# Quectel-1280.net
KiCad netlist of a schematic drawn in EAGLE
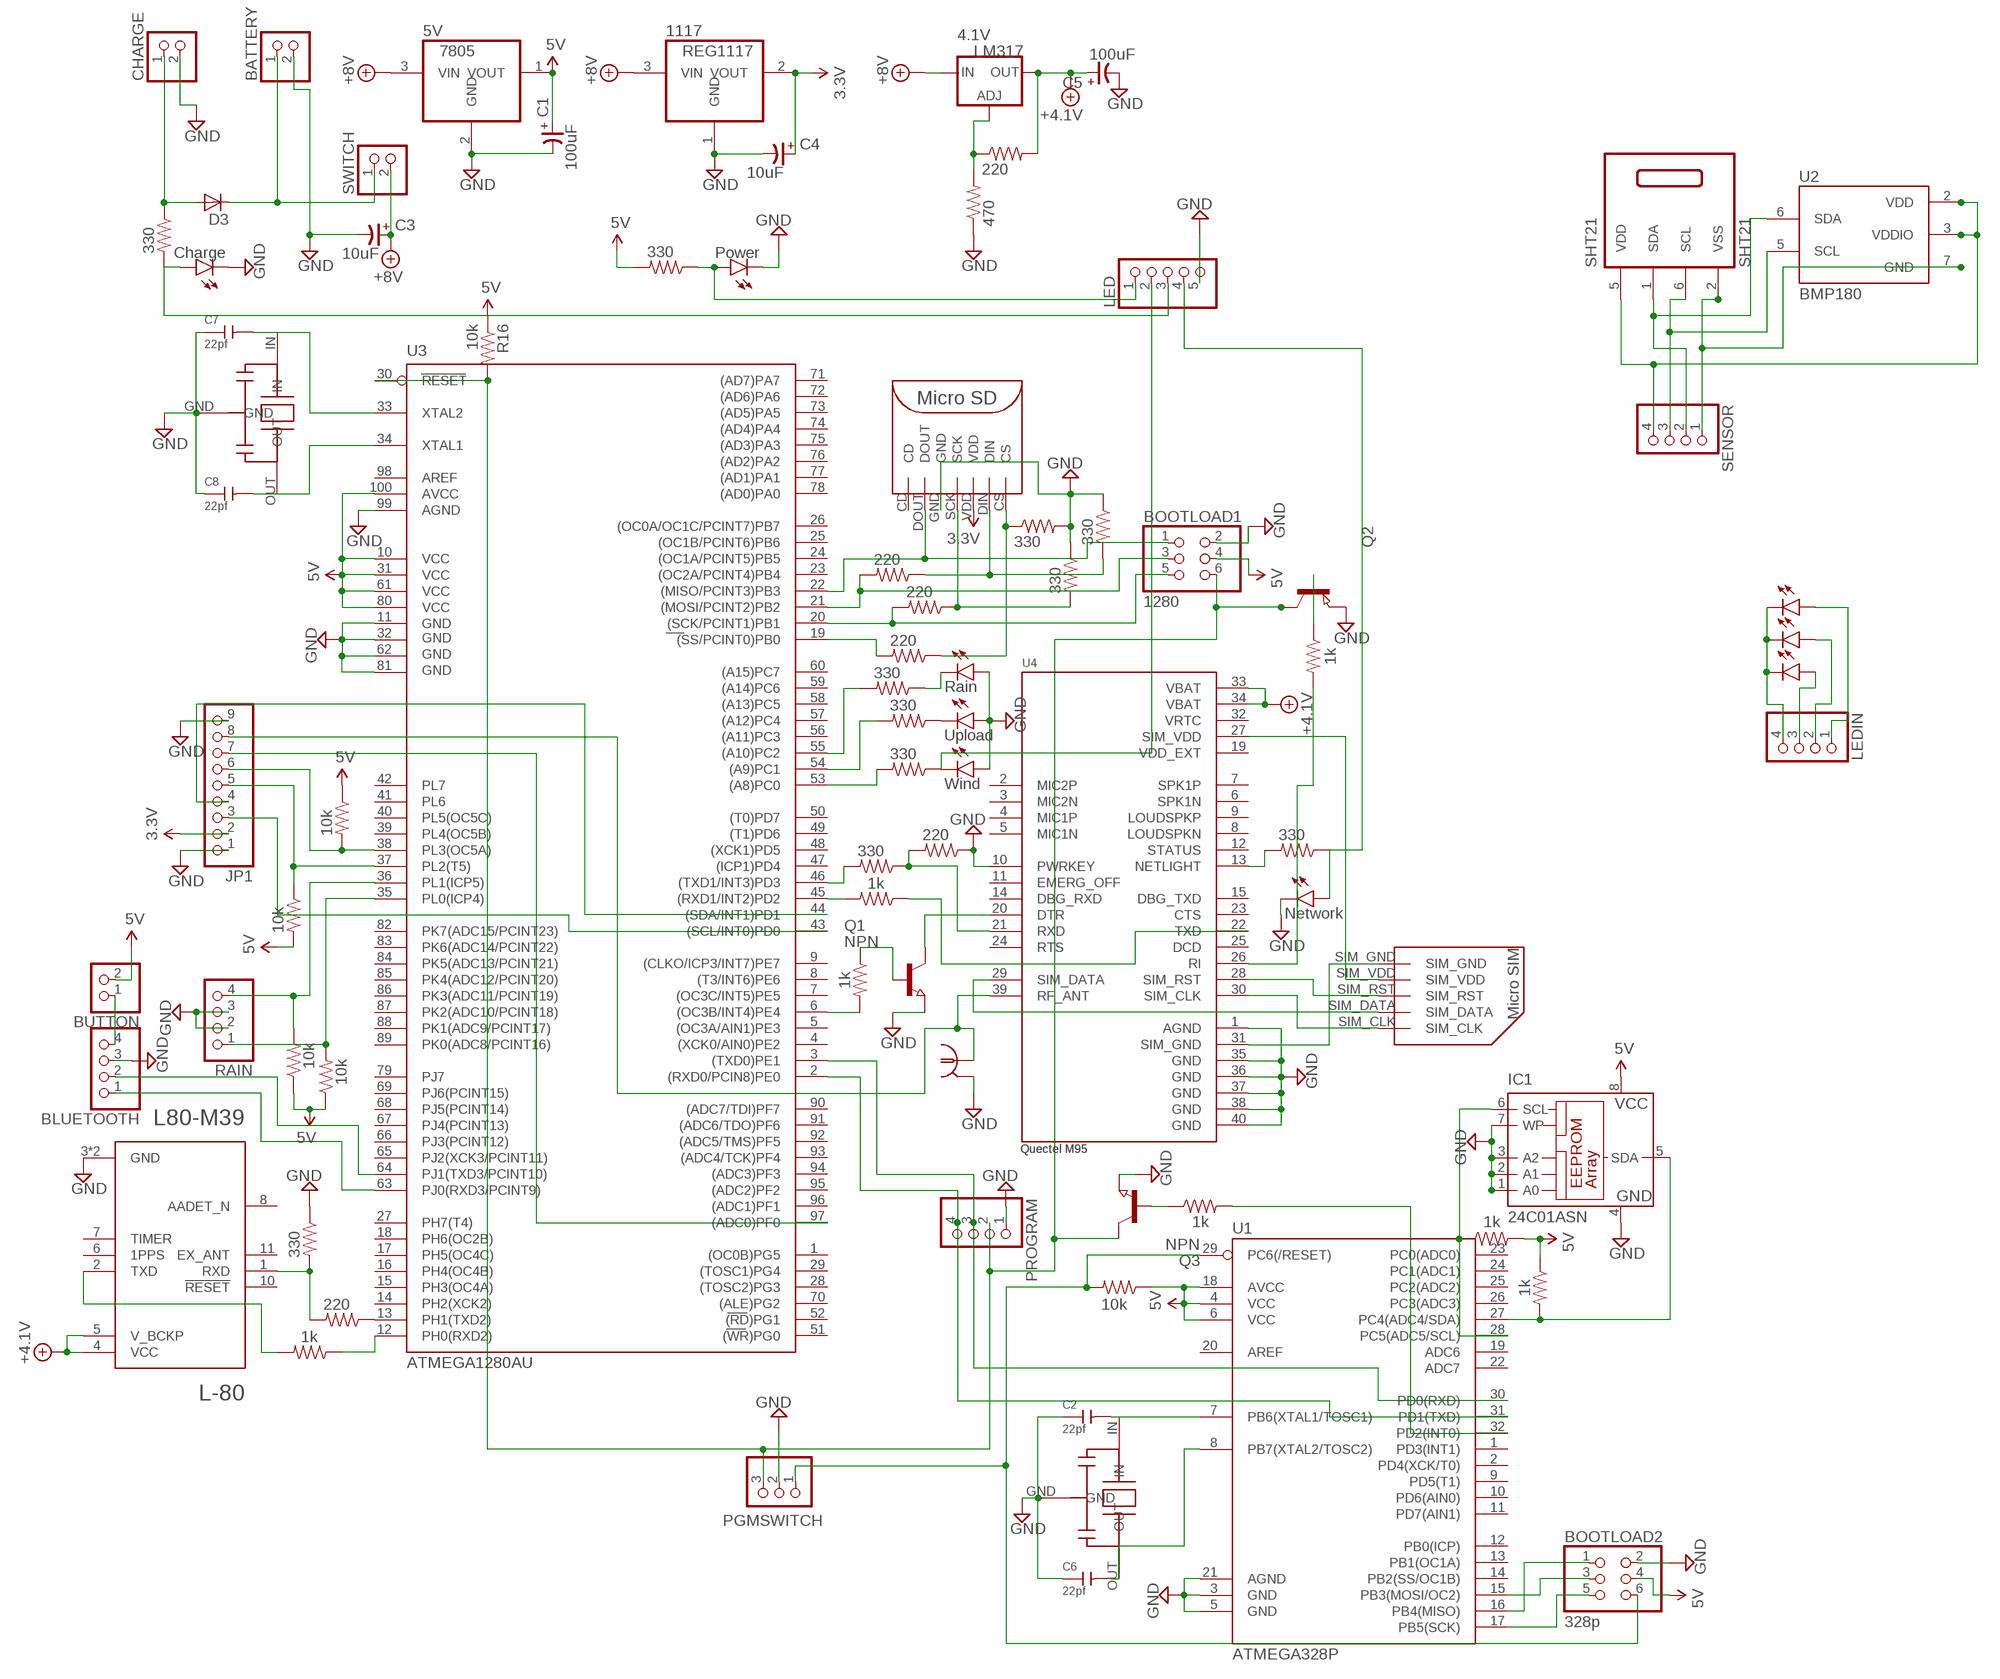
[diagram p0: schematic, sheet 1]

(export (version "E")
  (design (tool "Eeschema 10.0.6"))
  (components
    (comp (ref "4.1V")
      (value "LM317")
      (footprint "eagle-import:DPACK")
      (libsource (lib "eagle-import") (part "v-reg_LM317?MABDT"))
    )
    (comp (ref "5V")
      (value "7805")
      (footprint "eagle-import:SOT223")
      (fields (field (name "MPN") "REG1118-2.85/2K5G4") (field (name "MPN_1") "7805"))
      (libsource (lib "eagle-import") (part "REG1118"))
    )
    (comp (ref "1117")
      (value "REG1117")
      (footprint "eagle-import:SOT223")
      (libsource (lib "eagle-import") (part "REG1117"))
    )
    (comp (ref "ANT")
      (value "LTI-SASF54GT")
      (footprint "eagle-import:LTI-SASF54GT")
      (libsource (lib "eagle-import") (part "LTI-SASF54GT"))
    )
    (comp (ref "BATTERY")
      (value "PINHD-1X2")
      (footprint "eagle-import:1X02")
      (libsource (lib "eagle-import") (part "PINHD-1X2"))
    )
    (comp (ref "BLUETOOTH")
      (value "PINHD-1X4")
      (footprint "eagle-import:1X04")
      (libsource (lib "eagle-import") (part "PINHD-1X4"))
    )
    (comp (ref "BOOTLOAD1")
      (value "1280")
      (footprint "eagle-import:2X03")
      (libsource (lib "eagle-import") (part "PINHD-2X3"))
    )
    (comp (ref "BOOTLOAD2")
      (value "328p")
      (footprint "eagle-import:2X03")
      (libsource (lib "eagle-import") (part "PINHD-2X3"))
    )
    (comp (ref "BUTTON")
      (value "PINHD-1X2")
      (footprint "eagle-import:1X02")
      (libsource (lib "eagle-import") (part "PINHD-1X2"))
    )
    (comp (ref "C1")
      (value "100uF")
      (footprint "eagle-import:3528_T")
      (libsource (lib "eagle-import") (part "CP-3528"))
    )
    (comp (ref "C2")
      (value "22pf")
      (footprint "eagle-import:C0805")
      (fields (field (name "MPN") "CC0805JRNPO9BN220"))
      (libsource (lib "eagle-import") (part "CERAMIC-22PF-50V-5%-NPO(0805)"))
    )
    (comp (ref "C3")
      (value "10uF")
      (footprint "eagle-import:3528_T")
      (libsource (lib "eagle-import") (part "CP-3528"))
    )
    (comp (ref "C4")
      (value "10uF")
      (footprint "eagle-import:3528_T")
      (libsource (lib "eagle-import") (part "CP-3528"))
    )
    (comp (ref "C5")
      (value "100uF")
      (footprint "eagle-import:3528_T")
      (libsource (lib "eagle-import") (part "CP-3528"))
    )
    (comp (ref "C6")
      (value "22pf")
      (footprint "eagle-import:C0805")
      (fields (field (name "MPN") "CC0805JRNPO9BN220"))
      (libsource (lib "eagle-import") (part "CERAMIC-22PF-50V-5%-NPO(0805)"))
    )
    (comp (ref "C7")
      (value "22pf")
      (footprint "eagle-import:C0805")
      (fields (field (name "MPN") "CC0805JRNPO9BN220"))
      (libsource (lib "eagle-import") (part "CERAMIC-22PF-50V-5%-NPO(0805)"))
    )
    (comp (ref "C8")
      (value "22pf")
      (footprint "eagle-import:C0805")
      (fields (field (name "MPN") "CC0805JRNPO9BN220"))
      (libsource (lib "eagle-import") (part "CERAMIC-22PF-50V-5%-NPO(0805)"))
    )
    (comp (ref "CHARGE")
      (value "PINHD-1X2")
      (footprint "eagle-import:1X02")
      (libsource (lib "eagle-import") (part "PINHD-1X2"))
    )
    (comp (ref "D1")
      (value "Charge")
      (footprint "eagle-import:LED-1206")
      (libsource (lib "eagle-import") (part "LED-BLUE1206"))
    )
    (comp (ref "D2")
      (value "Rain")
      (footprint "eagle-import:LED-1206")
      (libsource (lib "eagle-import") (part "LED-BLUE1206"))
    )
    (comp (ref "D3")
      (value "BYS10")
      (footprint "eagle-import:SOD106A")
      (fields (field (name "MPN") "BYS10/45"))
      (libsource (lib "eagle-import") (part "BYS10"))
    )
    (comp (ref "D4")
      (value "Upload")
      (footprint "eagle-import:LED-1206")
      (libsource (lib "eagle-import") (part "LED-BLUE1206"))
    )
    (comp (ref "D5")
      (value "Power")
      (footprint "eagle-import:LED-1206")
      (libsource (lib "eagle-import") (part "LED-BLUE1206"))
    )
    (comp (ref "D6")
      (value "Network")
      (footprint "eagle-import:LED-1206")
      (libsource (lib "eagle-import") (part "LED-BLUE1206"))
    )
    (comp (ref "D7")
      (value "Wind")
      (footprint "eagle-import:LED-1206")
      (libsource (lib "eagle-import") (part "LED-BLUE1206"))
    )
    (comp (ref "D8")
      (value "LED-BLUE1206")
      (footprint "eagle-import:LED-1206")
      (libsource (lib "eagle-import") (part "LED-BLUE1206"))
    )
    (comp (ref "D9")
      (value "LED-BLUE1206")
      (footprint "eagle-import:LED-1206")
      (libsource (lib "eagle-import") (part "LED-BLUE1206"))
    )
    (comp (ref "D10")
      (value "LED-BLUE1206")
      (footprint "eagle-import:LED-1206")
      (libsource (lib "eagle-import") (part "LED-BLUE1206"))
    )
    (comp (ref "IC1")
      (value "24C01ASN")
      (footprint "eagle-import:SO-08")
      (fields (field (name "MPN") "AT24C01BN-SH-B"))
      (libsource (lib "eagle-import") (part "24CSN01A"))
    )
    (comp (ref "JP1")
      (value "PINHD-1X9")
      (footprint "eagle-import:1X09")
      (libsource (lib "eagle-import") (part "PINHD-1X9"))
    )
    (comp (ref "L-80")
      (value "L80-M39")
      (footprint "eagle-import:QUECTEL_L80-M39")
      (libsource (lib "eagle-import") (part "L80-M39"))
    )
    (comp (ref "LED")
      (value "PINHD-1X5")
      (footprint "eagle-import:1X05")
      (libsource (lib "eagle-import") (part "PINHD-1X5"))
    )
    (comp (ref "LEDIN")
      (value "PINHD-1X4")
      (footprint "eagle-import:1X04")
      (libsource (lib "eagle-import") (part "PINHD-1X4"))
    )
    (comp (ref "PGMSWITCH")
      (value "PINHD-1X3")
      (footprint "eagle-import:1X03")
      (libsource (lib "eagle-import") (part "PINHD-1X3"))
    )
    (comp (ref "PROGRAM")
      (value "PINHD-1X4")
      (footprint "eagle-import:1X04")
      (libsource (lib "eagle-import") (part "PINHD-1X4"))
    )
    (comp (ref "Q1")
      (value "NPN")
      (footprint "eagle-import:SOT23")
      (libsource (lib "eagle-import") (part "NPN-TRANSISTOR_SOT23"))
    )
    (comp (ref "Q2")
      (value "PNP-TRANSISTOR_SOT23")
      (footprint "eagle-import:SOT23")
      (libsource (lib "eagle-import") (part "PNP-TRANSISTOR_SOT23"))
    )
    (comp (ref "Q3")
      (value "NPN")
      (footprint "eagle-import:SOT23")
      (libsource (lib "eagle-import") (part "NPN-TRANSISTOR_SOT23"))
    )
    (comp (ref "R1")
      (value "10k")
      (footprint "eagle-import:0805")
      (libsource (lib "eagle-import") (part "RESISTOR0805-RES"))
    )
    (comp (ref "R2")
      (value "1k")
      (footprint "eagle-import:0805")
      (libsource (lib "eagle-import") (part "RESISTOR0805-RES"))
    )
    (comp (ref "R3")
      (value "1k")
      (footprint "eagle-import:0805")
      (libsource (lib "eagle-import") (part "RESISTOR0805-RES"))
    )
    (comp (ref "R4")
      (value "330")
      (footprint "eagle-import:0805")
      (libsource (lib "eagle-import") (part "RESISTOR0805-RES"))
    )
    (comp (ref "R5")
      (value "1k")
      (footprint "eagle-import:0805")
      (libsource (lib "eagle-import") (part "RESISTOR0805-RES"))
    )
    (comp (ref "R6")
      (value "220")
      (footprint "eagle-import:0805")
      (libsource (lib "eagle-import") (part "RESISTOR0805-RES"))
    )
    (comp (ref "R7")
      (value "220")
      (footprint "eagle-import:0805")
      (libsource (lib "eagle-import") (part "RESISTOR0805-RES"))
    )
    (comp (ref "R8")
      (value "220")
      (footprint "eagle-import:0805")
      (libsource (lib "eagle-import") (part "RESISTOR0805-RES"))
    )
    (comp (ref "R9")
      (value "330")
      (footprint "eagle-import:0805")
      (libsource (lib "eagle-import") (part "RESISTOR0805-RES"))
    )
    (comp (ref "R10")
      (value "220")
      (footprint "eagle-import:0805")
      (libsource (lib "eagle-import") (part "RESISTOR0805-RES"))
    )
    (comp (ref "R11")
      (value "470")
      (footprint "eagle-import:0805")
      (libsource (lib "eagle-import") (part "RESISTOR0805-RES"))
    )
    (comp (ref "R12")
      (value "220")
      (footprint "eagle-import:0805")
      (libsource (lib "eagle-import") (part "RESISTOR0805-RES"))
    )
    (comp (ref "R13")
      (value "1k")
      (footprint "eagle-import:0805")
      (libsource (lib "eagle-import") (part "RESISTOR0805-RES"))
    )
    (comp (ref "R14")
      (value "330")
      (footprint "eagle-import:0805")
      (libsource (lib "eagle-import") (part "RESISTOR0805-RES"))
    )
    (comp (ref "R15")
      (value "1k")
      (footprint "eagle-import:0805")
      (libsource (lib "eagle-import") (part "RESISTOR0805-RES"))
    )
    (comp (ref "R16")
      (value "10k")
      (footprint "eagle-import:0805")
      (libsource (lib "eagle-import") (part "RESISTOR0805-RES"))
    )
    (comp (ref "R17")
      (value "330")
      (footprint "eagle-import:0805")
      (libsource (lib "eagle-import") (part "RESISTOR0805-RES"))
    )
    (comp (ref "R18")
      (value "330")
      (footprint "eagle-import:0805")
      (libsource (lib "eagle-import") (part "RESISTOR0805-RES"))
    )
    (comp (ref "R19")
      (value "10k")
      (footprint "eagle-import:0805")
      (libsource (lib "eagle-import") (part "RESISTOR0805-RES"))
    )
    (comp (ref "R20")
      (value "10k")
      (footprint "eagle-import:0805")
      (libsource (lib "eagle-import") (part "RESISTOR0805-RES"))
    )
    (comp (ref "R21")
      (value "10k")
      (footprint "eagle-import:0805")
      (libsource (lib "eagle-import") (part "RESISTOR0805-RES"))
    )
    (comp (ref "R22")
      (value "10k")
      (footprint "eagle-import:0805")
      (libsource (lib "eagle-import") (part "RESISTOR0805-RES"))
    )
    (comp (ref "R23")
      (value "330")
      (footprint "eagle-import:0805")
      (libsource (lib "eagle-import") (part "RESISTOR0805-RES"))
    )
    (comp (ref "R24")
      (value "330")
      (footprint "eagle-import:0805")
      (libsource (lib "eagle-import") (part "RESISTOR0805-RES"))
    )
    (comp (ref "R25")
      (value "330")
      (footprint "eagle-import:0805")
      (libsource (lib "eagle-import") (part "RESISTOR0805-RES"))
    )
    (comp (ref "R26")
      (value "330")
      (footprint "eagle-import:0805")
      (libsource (lib "eagle-import") (part "RESISTOR0805-RES"))
    )
    (comp (ref "R27")
      (value "330")
      (footprint "eagle-import:0805")
      (libsource (lib "eagle-import") (part "RESISTOR0805-RES"))
    )
    (comp (ref "R28")
      (value "330")
      (footprint "eagle-import:0805")
      (libsource (lib "eagle-import") (part "RESISTOR0805-RES"))
    )
    (comp (ref "R29")
      (value "220")
      (footprint "eagle-import:0805")
      (libsource (lib "eagle-import") (part "RESISTOR0805-RES"))
    )
    (comp (ref "R30")
      (value "1k")
      (footprint "eagle-import:0805")
      (libsource (lib "eagle-import") (part "RESISTOR0805-RES"))
    )
    (comp (ref "R31")
      (value "1k")
      (footprint "eagle-import:0805")
      (libsource (lib "eagle-import") (part "RESISTOR0805-RES"))
    )
    (comp (ref "RAIN")
      (value "PINHD-1X4")
      (footprint "eagle-import:1X04")
      (libsource (lib "eagle-import") (part "PINHD-1X4"))
    )
    (comp (ref "SENSOR")
      (value "PINHD-1X4")
      (footprint "eagle-import:1X04")
      (libsource (lib "eagle-import") (part "PINHD-1X4"))
    )
    (comp (ref "SHT21")
      (value "SHT21")
      (footprint "eagle-import:DFN6_SHT")
      (libsource (lib "eagle-import") (part "SHT21"))
    )
    (comp (ref "SWITCH")
      (value "PINHD-1X2")
      (footprint "eagle-import:1X02")
      (libsource (lib "eagle-import") (part "PINHD-1X2"))
    )
    (comp (ref "U$1")
      (value "MICROSD")
      (footprint "eagle-import:MICROSD")
      (libsource (lib "eagle-import") (part "MICROSD"))
    )
    (comp (ref "U$2")
      (value "MICROSIM")
      (footprint "eagle-import:MICROSIM")
      (libsource (lib "eagle-import") (part "MICROSIM"))
    )
    (comp (ref "U1")
      (value "ATMEGA328P")
      (footprint "eagle-import:TQFP32-08")
      (libsource (lib "eagle-import") (part "ATMEGA328P_TQFP"))
    )
    (comp (ref "U2")
      (value "BMP180")
      (footprint "eagle-import:BMP180")
      (libsource (lib "eagle-import") (part "BMP180"))
    )
    (comp (ref "U3")
      (value "ATMEGA1280AU")
      (footprint "eagle-import:TQFP100")
      (libsource (lib "eagle-import") (part "ATMEGA2560AU"))
    )
    (comp (ref "U4")
      (value "Quectel M95")
      (footprint "eagle-import:XCVR_M95")
      (libsource (lib "eagle-import") (part "M95"))
    )
    (comp (ref "Y1")
      (value "CSTCE16M0V53-R0")
      (footprint "eagle-import:CFP95P160X100-3N")
      (libsource (lib "eagle-import") (part "CSTCE16M0V53-R0"))
    )
    (comp (ref "Y2")
      (value "CSTCE16M0V53-R0")
      (footprint "eagle-import:CFP95P160X100-3N")
      (libsource (lib "eagle-import") (part "CSTCE16M0V53-R0"))
    )
  )
  (nets
    (net (code "1") (name "+4.1V") (class "Default")
      (node (ref "4.1V") (pin "4") (pinfunction "OUT_4") (pintype "passive"))
      (node (ref "C5") (pin "+") (pinfunction "+_+") (pintype "passive"))
      (node (ref "L-80") (pin "4") (pinfunction "VCC_4") (pintype "power_in"))
      (node (ref "L-80") (pin "5") (pinfunction "V_BCKP_5") (pintype "power_in"))
      (node (ref "R10") (pin "2") (pinfunction "2_2") (pintype "passive"))
      (node (ref "U4") (pin "33") (pinfunction "VBAT_33") (pintype "power_in"))
      (node (ref "U4") (pin "34") (pinfunction "VBAT_34") (pintype "power_in"))
    )
    (net (code "2") (name "+8V") (class "Default")
      (node (ref "1117") (pin "3") (pinfunction "VIN_3") (pintype "input"))
      (node (ref "4.1V") (pin "3") (pinfunction "IN_3") (pintype "input"))
      (node (ref "5V") (pin "3") (pinfunction "VIN_3") (pintype "input"))
      (node (ref "C3") (pin "+") (pinfunction "+_+") (pintype "passive"))
      (node (ref "SWITCH") (pin "2") (pinfunction "2_2") (pintype "passive"))
    )
    (net (code "3") (name "/VDD_EXT") (class "Default")
      (node (ref "U4") (pin "19") (pinfunction "VDD_EXT_19") (pintype "power_in"))
    )
    (net (code "4") (name "/VRTC") (class "Default")
      (node (ref "U4") (pin "32") (pinfunction "VRTC_32") (pintype "power_in"))
    )
    (net (code "5") (name "3.3V") (class "Default")
      (node (ref "1117") (pin "2") (pinfunction "VOUT_2") (pintype "output"))
      (node (ref "C4") (pin "+") (pinfunction "+_+") (pintype "passive"))
      (node (ref "JP1") (pin "2") (pinfunction "2_2") (pintype "passive"))
      (node (ref "U$1") (pin "VDD") (pinfunction "VDD_VDD") (pintype "power_in"))
    )
    (net (code "6") (name "5V") (class "Default")
      (node (ref "5V") (pin "1") (pinfunction "VOUT_1") (pintype "output"))
      (node (ref "BOOTLOAD1") (pin "4") (pinfunction "4_4") (pintype "passive"))
      (node (ref "BOOTLOAD2") (pin "4") (pinfunction "4_4") (pintype "passive"))
      (node (ref "BUTTON") (pin "2") (pinfunction "2_2") (pintype "passive"))
      (node (ref "C1") (pin "+") (pinfunction "+_+") (pintype "passive"))
      (node (ref "IC1") (pin "8") (pinfunction "VCC_8") (pintype "power_in"))
      (node (ref "R1") (pin "1") (pinfunction "1_1") (pintype "passive"))
      (node (ref "R16") (pin "1") (pinfunction "1_1") (pintype "passive"))
      (node (ref "R18") (pin "2") (pinfunction "2_2") (pintype "passive"))
      (node (ref "R19") (pin "1") (pinfunction "1_1") (pintype "passive"))
      (node (ref "R20") (pin "2") (pinfunction "2_2") (pintype "passive"))
      (node (ref "R21") (pin "1") (pinfunction "1_1") (pintype "passive"))
      (node (ref "R22") (pin "1") (pinfunction "1_1") (pintype "passive"))
      (node (ref "R30") (pin "2") (pinfunction "2_2") (pintype "passive"))
      (node (ref "R5") (pin "1") (pinfunction "1_1") (pintype "passive"))
      (node (ref "U1") (pin "18") (pinfunction "AVCC_18") (pintype "bidirectional"))
      (node (ref "U1") (pin "4") (pinfunction "VCC_4") (pintype "bidirectional"))
      (node (ref "U1") (pin "6") (pinfunction "VCC_6") (pintype "bidirectional"))
      (node (ref "U3") (pin "10") (pinfunction "VCC_10") (pintype "power_in"))
      (node (ref "U3") (pin "100") (pinfunction "AVCC_100") (pintype "power_in"))
      (node (ref "U3") (pin "31") (pinfunction "VCC1_31") (pintype "power_in"))
      (node (ref "U3") (pin "61") (pinfunction "VCC2_61") (pintype "power_in"))
      (node (ref "U3") (pin "80") (pinfunction "VCC3_80") (pintype "power_in"))
    )
    (net (code "7") (name "GND") (class "Default")
      (node (ref "1117") (pin "1") (pinfunction "GND_1") (pintype "power_in"))
      (node (ref "5V") (pin "2") (pinfunction "GND_2") (pintype "power_in"))
      (node (ref "ANT") (pin "2") (pinfunction "2_2") (pintype "passive"))
      (node (ref "ANT") (pin "3") (pinfunction "2_3") (pintype "passive"))
      (node (ref "ANT") (pin "4") (pinfunction "2_4") (pintype "passive"))
      (node (ref "ANT") (pin "5") (pinfunction "2_5") (pintype "passive"))
      (node (ref "BATTERY") (pin "2") (pinfunction "2_2") (pintype "passive"))
      (node (ref "BLUETOOTH") (pin "3") (pinfunction "3_3") (pintype "passive"))
      (node (ref "BOOTLOAD1") (pin "2") (pinfunction "2_2") (pintype "passive"))
      (node (ref "BOOTLOAD2") (pin "2") (pinfunction "2_2") (pintype "passive"))
      (node (ref "C1") (pin "-") (pinfunction "-_-") (pintype "passive"))
      (node (ref "C2") (pin "1") (pinfunction "1_1") (pintype "passive"))
      (node (ref "C3") (pin "-") (pinfunction "-_-") (pintype "passive"))
      (node (ref "C4") (pin "-") (pinfunction "-_-") (pintype "passive"))
      (node (ref "C5") (pin "-") (pinfunction "-_-") (pintype "passive"))
      (node (ref "C6") (pin "1") (pinfunction "1_1") (pintype "passive"))
      (node (ref "C7") (pin "1") (pinfunction "1_1") (pintype "passive"))
      (node (ref "C8") (pin "1") (pinfunction "1_1") (pintype "passive"))
      (node (ref "CHARGE") (pin "2") (pinfunction "2_2") (pintype "passive"))
      (node (ref "D1") (pin "C") (pinfunction "C_C") (pintype "passive"))
      (node (ref "D2") (pin "A") (pinfunction "A_A") (pintype "passive"))
      (node (ref "D4") (pin "A") (pinfunction "A_A") (pintype "passive"))
      (node (ref "D5") (pin "C") (pinfunction "C_C") (pintype "passive"))
      (node (ref "D6") (pin "C") (pinfunction "C_C") (pintype "passive"))
      (node (ref "D7") (pin "A") (pinfunction "A_A") (pintype "passive"))
      (node (ref "IC1") (pin "1") (pinfunction "A0_1") (pintype "input"))
      (node (ref "IC1") (pin "2") (pinfunction "A1_2") (pintype "input"))
      (node (ref "IC1") (pin "3") (pinfunction "A2_3") (pintype "input"))
      (node (ref "IC1") (pin "4") (pinfunction "GND_4") (pintype "power_in"))
      (node (ref "IC1") (pin "7") (pinfunction "WP_7") (pintype "input"))
      (node (ref "JP1") (pin "1") (pinfunction "1_1") (pintype "passive"))
      (node (ref "JP1") (pin "9") (pinfunction "9_9") (pintype "passive"))
      (node (ref "L-80") (pin "12") (pinfunction "GND_12") (pintype "passive"))
      (node (ref "L-80") (pin "3") (pinfunction "GND_3") (pintype "passive"))
      (node (ref "LED") (pin "5") (pinfunction "5_5") (pintype "passive"))
      (node (ref "PGMSWITCH") (pin "2") (pinfunction "2_2") (pintype "passive"))
      (node (ref "PROGRAM") (pin "1") (pinfunction "1_1") (pintype "passive"))
      (node (ref "Q1") (pin "2") (pinfunction "E_2") (pintype "passive"))
      (node (ref "Q2") (pin "2") (pinfunction "E_2") (pintype "passive"))
      (node (ref "Q3") (pin "2") (pinfunction "E_2") (pintype "passive"))
      (node (ref "R11") (pin "1") (pinfunction "1_1") (pintype "passive"))
      (node (ref "R23") (pin "2") (pinfunction "2_2") (pintype "passive"))
      (node (ref "R24") (pin "1") (pinfunction "1_1") (pintype "passive"))
      (node (ref "R29") (pin "1") (pinfunction "1_1") (pintype "passive"))
      (node (ref "R4") (pin "1") (pinfunction "1_1") (pintype "passive"))
      (node (ref "R9") (pin "1") (pinfunction "1_1") (pintype "passive"))
      (node (ref "RAIN") (pin "2") (pinfunction "2_2") (pintype "passive"))
      (node (ref "RAIN") (pin "3") (pinfunction "3_3") (pintype "passive"))
      (node (ref "U$1") (pin "GND") (pinfunction "GND_GND") (pintype "power_in"))
      (node (ref "U1") (pin "21") (pinfunction "AGND_21") (pintype "bidirectional"))
      (node (ref "U1") (pin "3") (pinfunction "GND_3") (pintype "bidirectional"))
      (node (ref "U1") (pin "5") (pinfunction "GND_5") (pintype "bidirectional"))
      (node (ref "U3") (pin "11") (pinfunction "GND_11") (pintype "power_in"))
      (node (ref "U3") (pin "32") (pinfunction "GND1_32") (pintype "power_in"))
      (node (ref "U3") (pin "62") (pinfunction "GND2_62") (pintype "power_in"))
      (node (ref "U3") (pin "81") (pinfunction "GND3_81") (pintype "power_in"))
      (node (ref "U3") (pin "99") (pinfunction "AGND_99") (pintype "power_in"))
      (node (ref "U4") (pin "1") (pinfunction "AGND_1") (pintype "power_in"))
      (node (ref "U4") (pin "10") (pinfunction "PWRKEY_10") (pintype "input"))
      (node (ref "U4") (pin "35") (pinfunction "GND_35") (pintype "power_in"))
      (node (ref "U4") (pin "36") (pinfunction "GND_36") (pintype "power_in"))
      (node (ref "U4") (pin "37") (pinfunction "GND_37") (pintype "power_in"))
      (node (ref "U4") (pin "38") (pinfunction "GND_38") (pintype "input"))
      (node (ref "U4") (pin "40") (pinfunction "GND_40") (pintype "power_in"))
      (node (ref "Y1") (pin "GND") (pinfunction "GND_GND") (pintype "passive"))
      (node (ref "Y2") (pin "GND") (pinfunction "GND_GND") (pintype "passive"))
    )
    (net (code "8") (name "Net-(4.1V-ADJ)") (class "Default")
      (node (ref "4.1V") (pin "1") (pinfunction "ADJ_1") (pintype "input"))
      (node (ref "R10") (pin "1") (pinfunction "1_1") (pintype "passive"))
      (node (ref "R11") (pin "2") (pinfunction "2_2") (pintype "passive"))
    )
    (net (code "9") (name "Net-(BATTERY-Pad1)") (class "Default")
      (node (ref "BATTERY") (pin "1") (pinfunction "1_1") (pintype "passive"))
      (node (ref "D3") (pin "K") (pinfunction "K_K") (pintype "passive"))
      (node (ref "SWITCH") (pin "1") (pinfunction "1_1") (pintype "passive"))
    )
    (net (code "10") (name "Net-(BLUETOOTH-Pad4)") (class "Default")
      (node (ref "BLUETOOTH") (pin "4") (pinfunction "4_4") (pintype "passive"))
      (node (ref "BUTTON") (pin "1") (pinfunction "1_1") (pintype "passive"))
    )
    (net (code "11") (name "Net-(CHARGE-Pad1)") (class "Default")
      (node (ref "CHARGE") (pin "1") (pinfunction "1_1") (pintype "passive"))
      (node (ref "D3") (pin "A") (pinfunction "A_A") (pintype "passive"))
      (node (ref "R26") (pin "1") (pinfunction "1_1") (pintype "passive"))
    )
    (net (code "12") (name "Net-(D1-PadA)") (class "Default")
      (node (ref "D1") (pin "A") (pinfunction "A_A") (pintype "passive"))
      (node (ref "LED") (pin "3") (pinfunction "3_3") (pintype "passive"))
      (node (ref "R26") (pin "2") (pinfunction "2_2") (pintype "passive"))
    )
    (net (code "13") (name "Net-(D2-PadC)") (class "Default")
      (node (ref "D2") (pin "C") (pinfunction "C_C") (pintype "passive"))
      (node (ref "R27") (pin "1") (pinfunction "1_1") (pintype "passive"))
    )
    (net (code "14") (name "Net-(D4-PadC)") (class "Default")
      (node (ref "D4") (pin "C") (pinfunction "C_C") (pintype "passive"))
      (node (ref "R25") (pin "1") (pinfunction "1_1") (pintype "passive"))
    )
    (net (code "15") (name "Net-(D5-PadA)") (class "Default")
      (node (ref "D5") (pin "A") (pinfunction "A_A") (pintype "passive"))
      (node (ref "LED") (pin "1") (pinfunction "1_1") (pintype "passive"))
      (node (ref "R18") (pin "1") (pinfunction "1_1") (pintype "passive"))
    )
    (net (code "16") (name "Net-(D6-PadA)") (class "Default")
      (node (ref "D6") (pin "A") (pinfunction "A_A") (pintype "passive"))
      (node (ref "LED") (pin "4") (pinfunction "4_4") (pintype "passive"))
      (node (ref "R17") (pin "1") (pinfunction "1_1") (pintype "passive"))
    )
    (net (code "17") (name "Net-(D7-PadC)") (class "Default")
      (node (ref "D7") (pin "C") (pinfunction "C_C") (pintype "passive"))
      (node (ref "LED") (pin "2") (pinfunction "2_2") (pintype "passive"))
      (node (ref "R28") (pin "1") (pinfunction "1_1") (pintype "passive"))
    )
    (net (code "18") (name "Net-(D8-PadA)") (class "Default")
      (node (ref "D8") (pin "A") (pinfunction "A_A") (pintype "passive"))
      (node (ref "LEDIN") (pin "2") (pinfunction "2_2") (pintype "passive"))
    )
    (net (code "19") (name "Net-(D9-PadA)") (class "Default")
      (node (ref "D9") (pin "A") (pinfunction "A_A") (pintype "passive"))
      (node (ref "LEDIN") (pin "1") (pinfunction "1_1") (pintype "passive"))
    )
    (net (code "20") (name "Net-(D10-PadA)") (class "Default")
      (node (ref "D10") (pin "A") (pinfunction "A_A") (pintype "passive"))
      (node (ref "LEDIN") (pin "3") (pinfunction "3_3") (pintype "passive"))
    )
    (net (code "21") (name "Net-(D10-PadC)") (class "Default")
      (node (ref "D10") (pin "C") (pinfunction "C_C") (pintype "passive"))
      (node (ref "D8") (pin "C") (pinfunction "C_C") (pintype "passive"))
      (node (ref "D9") (pin "C") (pinfunction "C_C") (pintype "passive"))
      (node (ref "LEDIN") (pin "4") (pinfunction "4_4") (pintype "passive"))
    )
    (net (code "22") (name "Net-(IC1-SCL)") (class "Default")
      (node (ref "IC1") (pin "6") (pinfunction "SCL_6") (pintype "input"))
      (node (ref "R30") (pin "1") (pinfunction "1_1") (pintype "passive"))
      (node (ref "U1") (pin "28") (pinfunction "PC5(ADC5/SCL)_28") (pintype "bidirectional"))
    )
    (net (code "23") (name "Net-(IC1-SDA)") (class "Default")
      (node (ref "IC1") (pin "5") (pinfunction "SDA_5") (pintype "bidirectional"))
      (node (ref "R5") (pin "2") (pinfunction "2_2") (pintype "passive"))
      (node (ref "U1") (pin "27") (pinfunction "PC4(ADC4/SDA)_27") (pintype "bidirectional"))
    )
    (net (code "24") (name "Net-(L-80-RXD)") (class "Default")
      (node (ref "L-80") (pin "1") (pinfunction "RXD_1") (pintype "input"))
      (node (ref "R12") (pin "2") (pinfunction "2_2") (pintype "passive"))
      (node (ref "R4") (pin "2") (pinfunction "2_2") (pintype "passive"))
    )
    (net (code "25") (name "Net-(L-80-TXD)") (class "Default")
      (node (ref "L-80") (pin "2") (pinfunction "TXD_2") (pintype "output"))
      (node (ref "R13") (pin "2") (pinfunction "2_2") (pintype "passive"))
    )
    (net (code "26") (name "Net-(Q1-B)") (class "Default")
      (node (ref "Q1") (pin "1") (pinfunction "B_1") (pintype "passive"))
      (node (ref "R2") (pin "1") (pinfunction "1_1") (pintype "passive"))
    )
    (net (code "27") (name "Net-(Q1-C)") (class "Default")
      (node (ref "Q1") (pin "3") (pinfunction "C_3") (pintype "passive"))
      (node (ref "U4") (pin "20") (pinfunction "DTR_20") (pintype "input"))
    )
    (net (code "28") (name "Net-(Q2-B)") (class "Default")
      (node (ref "Q2") (pin "1") (pinfunction "B_1") (pintype "passive"))
      (node (ref "R3") (pin "1") (pinfunction "1_1") (pintype "passive"))
    )
    (net (code "29") (name "Net-(Q2-C)") (class "Default")
      (node (ref "BOOTLOAD1") (pin "6") (pinfunction "6_6") (pintype "passive"))
      (node (ref "PGMSWITCH") (pin "3") (pinfunction "3_3") (pintype "passive"))
      (node (ref "PROGRAM") (pin "2") (pinfunction "2_2") (pintype "passive"))
      (node (ref "Q2") (pin "3") (pinfunction "C_3") (pintype "passive"))
      (node (ref "Q3") (pin "3") (pinfunction "C_3") (pintype "passive"))
      (node (ref "R16") (pin "2") (pinfunction "2_2") (pintype "passive"))
      (node (ref "U3") (pin "30") (pinfunction "RESET_30") (pintype "input"))
    )
    (net (code "30") (name "Net-(Q3-B)") (class "Default")
      (node (ref "Q3") (pin "1") (pinfunction "B_1") (pintype "passive"))
      (node (ref "R31") (pin "1") (pinfunction "1_1") (pintype "passive"))
    )
    (net (code "31") (name "Net-(R6-Pad1)") (class "Default")
      (node (ref "R6") (pin "1") (pinfunction "1_1") (pintype "passive"))
      (node (ref "R9") (pin "2") (pinfunction "2_2") (pintype "passive"))
      (node (ref "U$1") (pin "DIN") (pinfunction "DIN_DIN") (pintype "input"))
    )
    (net (code "32") (name "Net-(R23-Pad1)") (class "Default")
      (node (ref "R23") (pin "1") (pinfunction "1_1") (pintype "passive"))
      (node (ref "R8") (pin "1") (pinfunction "1_1") (pintype "passive"))
      (node (ref "U$1") (pin "CS") (pinfunction "CS_CS") (pintype "bidirectional"))
    )
    (net (code "33") (name "Net-(R24-Pad2)") (class "Default")
      (node (ref "R24") (pin "2") (pinfunction "2_2") (pintype "passive"))
      (node (ref "R7") (pin "1") (pinfunction "1_1") (pintype "passive"))
      (node (ref "U$1") (pin "SCK") (pinfunction "SCK_SCK") (pintype "bidirectional"))
    )
    (net (code "34") (name "Net-(SHT21-SCL)") (class "Default")
      (node (ref "SENSOR") (pin "3") (pinfunction "3_3") (pintype "passive"))
      (node (ref "SHT21") (pin "6") (pinfunction "SCL_6") (pintype "bidirectional"))
      (node (ref "U2") (pin "5") (pinfunction "SCL_5") (pintype "input"))
    )
    (net (code "35") (name "Net-(SHT21-SDA)") (class "Default")
      (node (ref "SENSOR") (pin "2") (pinfunction "2_2") (pintype "passive"))
      (node (ref "SHT21") (pin "1") (pinfunction "SDA_1") (pintype "bidirectional"))
      (node (ref "U2") (pin "6") (pinfunction "SDA_6") (pintype "bidirectional"))
    )
    (net (code "36") (name "Net-(SHT21-VDD)") (class "Default")
      (node (ref "SENSOR") (pin "4") (pinfunction "4_4") (pintype "passive"))
      (node (ref "SHT21") (pin "5") (pinfunction "VDD_5") (pintype "power_in"))
      (node (ref "U2") (pin "2") (pinfunction "VDD_2") (pintype "power_in"))
      (node (ref "U2") (pin "3") (pinfunction "VDDIO_3") (pintype "power_in"))
    )
    (net (code "37") (name "Net-(SHT21-VSS)") (class "Default")
      (node (ref "SENSOR") (pin "1") (pinfunction "1_1") (pintype "passive"))
      (node (ref "SHT21") (pin "2") (pinfunction "VSS_2") (pintype "power_in"))
      (node (ref "U2") (pin "7") (pinfunction "GND_7") (pintype "power_in"))
    )
    (net (code "38") (name "Net-(U1-PB3(MOSI{slash}OC2))") (class "Default")
      (node (ref "BOOTLOAD2") (pin "3") (pinfunction "3_3") (pintype "passive"))
      (node (ref "U1") (pin "15") (pinfunction "PB3(MOSI/OC2)_15") (pintype "bidirectional"))
    )
    (net (code "39") (name "Net-(U1-PB4(MISO))") (class "Default")
      (node (ref "BOOTLOAD2") (pin "1") (pinfunction "1_1") (pintype "passive"))
      (node (ref "U1") (pin "16") (pinfunction "PB4(MISO)_16") (pintype "bidirectional"))
    )
    (net (code "40") (name "Net-(U1-PB5(SCK))") (class "Default")
      (node (ref "BOOTLOAD2") (pin "5") (pinfunction "5_5") (pintype "passive"))
      (node (ref "U1") (pin "17") (pinfunction "PB5(SCK)_17") (pintype "bidirectional"))
    )
    (net (code "41") (name "Net-(U1-PB6(XTAL1{slash}TOSC1))") (class "Default")
      (node (ref "C2") (pin "2") (pinfunction "2_2") (pintype "passive"))
      (node (ref "U1") (pin "7") (pinfunction "PB6(XTAL1/TOSC1)_7") (pintype "bidirectional"))
      (node (ref "Y1") (pin "IN") (pinfunction "IN_IN") (pintype "input"))
    )
    (net (code "42") (name "Net-(U1-PB7(XTAL2{slash}TOSC2))") (class "Default")
      (node (ref "C6") (pin "2") (pinfunction "2_2") (pintype "passive"))
      (node (ref "U1") (pin "8") (pinfunction "PB7(XTAL2/TOSC2)_8") (pintype "bidirectional"))
      (node (ref "Y1") (pin "OUT") (pinfunction "OUT_OUT") (pintype "output"))
    )
    (net (code "43") (name "Net-(U1-PC6({slash}RESET))") (class "Default")
      (node (ref "BOOTLOAD2") (pin "6") (pinfunction "6_6") (pintype "passive"))
      (node (ref "PGMSWITCH") (pin "1") (pinfunction "1_1") (pintype "passive"))
      (node (ref "R1") (pin "2") (pinfunction "2_2") (pintype "passive"))
      (node (ref "U1") (pin "29") (pinfunction "PC6(/RESET)_29") (pintype "bidirectional"))
    )
    (net (code "44") (name "Net-(U1-PD0(RXD))") (class "Default")
      (node (ref "PROGRAM") (pin "3") (pinfunction "3_3") (pintype "passive"))
      (node (ref "U1") (pin "30") (pinfunction "PD0(RXD)_30") (pintype "bidirectional"))
      (node (ref "U3") (pin "3") (pinfunction "(TXD0)PE1_3") (pintype "bidirectional"))
    )
    (net (code "45") (name "Net-(U1-PD1(TXD))") (class "Default")
      (node (ref "PROGRAM") (pin "4") (pinfunction "4_4") (pintype "passive"))
      (node (ref "U1") (pin "31") (pinfunction "PD1(TXD)_31") (pintype "bidirectional"))
      (node (ref "U3") (pin "2") (pinfunction "(RXD0/PCIN8)PE0_2") (pintype "bidirectional"))
    )
    (net (code "46") (name "Net-(U1-PD2(INT0))") (class "Default")
      (node (ref "R31") (pin "2") (pinfunction "2_2") (pintype "passive"))
      (node (ref "U1") (pin "32") (pinfunction "PD2(INT0)_32") (pintype "bidirectional"))
    )
    (net (code "47") (name "Net-(U3-(A8)PC0)") (class "Default")
      (node (ref "R28") (pin "2") (pinfunction "2_2") (pintype "passive"))
      (node (ref "U3") (pin "53") (pinfunction "(A8)PC0_53") (pintype "bidirectional"))
    )
    (net (code "48") (name "Net-(U3-(A9)PC1)") (class "Default")
      (node (ref "R25") (pin "2") (pinfunction "2_2") (pintype "passive"))
      (node (ref "U3") (pin "54") (pinfunction "(A9)PC1_54") (pintype "bidirectional"))
    )
    (net (code "49") (name "Net-(U3-(A10)PC2)") (class "Default")
      (node (ref "R27") (pin "2") (pinfunction "2_2") (pintype "passive"))
      (node (ref "U3") (pin "55") (pinfunction "(A10)PC2_55") (pintype "bidirectional"))
    )
    (net (code "50") (name "Net-(U3-(ADC0)PF0)") (class "Default")
      (node (ref "JP1") (pin "7") (pinfunction "7_7") (pintype "passive"))
      (node (ref "U3") (pin "97") (pinfunction "(ADC0)PF0_97") (pintype "bidirectional"))
    )
    (net (code "51") (name "Net-(U3-(MISO{slash}PCINT3)PB3)") (class "Default")
      (node (ref "BOOTLOAD1") (pin "1") (pinfunction "1_1") (pintype "passive"))
      (node (ref "U$1") (pin "DOUT") (pinfunction "DOUT_DOUT") (pintype "output"))
      (node (ref "U3") (pin "22") (pinfunction "(MISO/PCINT3)PB3_22") (pintype "bidirectional"))
    )
    (net (code "52") (name "Net-(U3-(MOSI{slash}PCINT2)PB2)") (class "Default")
      (node (ref "BOOTLOAD1") (pin "3") (pinfunction "3_3") (pintype "passive"))
      (node (ref "R6") (pin "2") (pinfunction "2_2") (pintype "passive"))
      (node (ref "U3") (pin "21") (pinfunction "(MOSI/PCINT2)PB2_21") (pintype "bidirectional"))
    )
    (net (code "53") (name "Net-(U3-(OC3B{slash}INT4)PE4)") (class "Default")
      (node (ref "R2") (pin "2") (pinfunction "2_2") (pintype "passive"))
      (node (ref "U3") (pin "6") (pinfunction "(OC3B/INT4)PE4_6") (pintype "bidirectional"))
    )
    (net (code "54") (name "Net-(U3-(RXD1{slash}INT2)PD2)") (class "Default")
      (node (ref "R15") (pin "2") (pinfunction "2_2") (pintype "passive"))
      (node (ref "U3") (pin "45") (pinfunction "(RXD1/INT2)PD2_45") (pintype "bidirectional"))
    )
    (net (code "55") (name "Net-(U3-(SCK{slash}PCINT1)PB1)") (class "Default")
      (node (ref "BOOTLOAD1") (pin "5") (pinfunction "5_5") (pintype "passive"))
      (node (ref "R7") (pin "2") (pinfunction "2_2") (pintype "passive"))
      (node (ref "U3") (pin "20") (pinfunction "(SCK/PCINT1)PB1_20") (pintype "bidirectional"))
    )
    (net (code "56") (name "Net-(U3-(SCL{slash}INT0)PD0)") (class "Default")
      (node (ref "JP1") (pin "3") (pinfunction "3_3") (pintype "passive"))
      (node (ref "U3") (pin "43") (pinfunction "(SCL/INT0)PD0_43") (pintype "bidirectional"))
    )
    (net (code "57") (name "Net-(U3-(SDA{slash}INT1)PD1)") (class "Default")
      (node (ref "JP1") (pin "4") (pinfunction "4_4") (pintype "passive"))
      (node (ref "U3") (pin "44") (pinfunction "(SDA/INT1)PD1_44") (pintype "bidirectional"))
    )
    (net (code "58") (name "Net-(U3-(SS{slash}PCINT0)PB0)") (class "Default")
      (node (ref "R8") (pin "2") (pinfunction "2_2") (pintype "passive"))
      (node (ref "U3") (pin "19") (pinfunction "(SS/PCINT0)PB0_19") (pintype "bidirectional"))
    )
    (net (code "59") (name "Net-(U3-(TXD1{slash}INT3)PD3)") (class "Default")
      (node (ref "R14") (pin "2") (pinfunction "2_2") (pintype "passive"))
      (node (ref "U3") (pin "46") (pinfunction "(TXD1/INT3)PD3_46") (pintype "bidirectional"))
    )
    (net (code "60") (name "Net-(U3-PH0(RXD2))") (class "Default")
      (node (ref "R13") (pin "1") (pinfunction "1_1") (pintype "passive"))
      (node (ref "U3") (pin "12") (pinfunction "PH0(RXD2)_12") (pintype "bidirectional"))
    )
    (net (code "61") (name "Net-(U3-PH1(TXD2))") (class "Default")
      (node (ref "R12") (pin "1") (pinfunction "1_1") (pintype "passive"))
      (node (ref "U3") (pin "13") (pinfunction "PH1(TXD2)_13") (pintype "bidirectional"))
    )
    (net (code "62") (name "Net-(U3-PJ0(RXD3{slash}PCINT9))") (class "Default")
      (node (ref "BLUETOOTH") (pin "1") (pinfunction "1_1") (pintype "passive"))
      (node (ref "U3") (pin "63") (pinfunction "PJ0(RXD3/PCINT9)_63") (pintype "bidirectional"))
    )
    (net (code "63") (name "Net-(U3-PJ1(TXD3{slash}PCINT10))") (class "Default")
      (node (ref "BLUETOOTH") (pin "2") (pinfunction "2_2") (pintype "passive"))
      (node (ref "U3") (pin "64") (pinfunction "PJ1(TXD3/PCINT10)_64") (pintype "bidirectional"))
    )
    (net (code "64") (name "Net-(U3-PL0(ICP4))") (class "Default")
      (node (ref "R22") (pin "2") (pinfunction "2_2") (pintype "passive"))
      (node (ref "RAIN") (pin "1") (pinfunction "1_1") (pintype "passive"))
      (node (ref "U3") (pin "35") (pinfunction "PL0(ICP4)_35") (pintype "bidirectional"))
    )
    (net (code "65") (name "Net-(U3-PL1(ICP5))") (class "Default")
      (node (ref "R21") (pin "2") (pinfunction "2_2") (pintype "passive"))
      (node (ref "RAIN") (pin "4") (pinfunction "4_4") (pintype "passive"))
      (node (ref "U3") (pin "36") (pinfunction "PL1(ICP5)_36") (pintype "bidirectional"))
    )
    (net (code "66") (name "Net-(U3-PL2(T5))") (class "Default")
      (node (ref "JP1") (pin "5") (pinfunction "5_5") (pintype "passive"))
      (node (ref "R20") (pin "1") (pinfunction "1_1") (pintype "passive"))
      (node (ref "U3") (pin "37") (pinfunction "PL2(T5)_37") (pintype "bidirectional"))
    )
    (net (code "67") (name "Net-(U3-PL3(OC5A))") (class "Default")
      (node (ref "JP1") (pin "6") (pinfunction "6_6") (pintype "passive"))
      (node (ref "R19") (pin "2") (pinfunction "2_2") (pintype "passive"))
      (node (ref "U3") (pin "38") (pinfunction "PL3(OC5A)_38") (pintype "bidirectional"))
    )
    (net (code "68") (name "Net-(U3-XTAL1)") (class "Default")
      (node (ref "C8") (pin "2") (pinfunction "2_2") (pintype "passive"))
      (node (ref "U3") (pin "34") (pinfunction "XTAL1_34") (pintype "input"))
      (node (ref "Y2") (pin "OUT") (pinfunction "OUT_OUT") (pintype "output"))
    )
    (net (code "69") (name "Net-(U3-XTAL2)") (class "Default")
      (node (ref "C7") (pin "2") (pinfunction "2_2") (pintype "passive"))
      (node (ref "U3") (pin "33") (pinfunction "XTAL2_33") (pintype "output"))
      (node (ref "Y2") (pin "IN") (pinfunction "IN_IN") (pintype "input"))
    )
    (net (code "70") (name "Net-(U4-NETLIGHT)") (class "Default")
      (node (ref "R17") (pin "2") (pinfunction "2_2") (pintype "passive"))
      (node (ref "U4") (pin "13") (pinfunction "NETLIGHT_13") (pintype "output"))
    )
    (net (code "71") (name "Net-(U4-RF_ANT)") (class "Default")
      (node (ref "ANT") (pin "1") (pinfunction "1_1") (pintype "passive"))
      (node (ref "JP1") (pin "8") (pinfunction "8_8") (pintype "passive"))
      (node (ref "U4") (pin "39") (pinfunction "RF_ANT_39") (pintype "bidirectional"))
    )
    (net (code "72") (name "Net-(U4-RI)") (class "Default")
      (node (ref "R3") (pin "2") (pinfunction "2_2") (pintype "passive"))
      (node (ref "U4") (pin "26") (pinfunction "RI_26") (pintype "output"))
    )
    (net (code "73") (name "Net-(U4-RXD)") (class "Default")
      (node (ref "R14") (pin "1") (pinfunction "1_1") (pintype "passive"))
      (node (ref "R29") (pin "2") (pinfunction "2_2") (pintype "passive"))
      (node (ref "U4") (pin "21") (pinfunction "RXD_21") (pintype "input"))
    )
    (net (code "74") (name "Net-(U4-SIM_CLK)") (class "Default")
      (node (ref "U$2") (pin "SIM_CLK") (pinfunction "SIM_CLK_SIM_CLK") (pintype "bidirectional"))
      (node (ref "U4") (pin "30") (pinfunction "SIM_CLK_30") (pintype "output"))
    )
    (net (code "75") (name "Net-(U4-SIM_DATA)") (class "Default")
      (node (ref "U$2") (pin "SIM_DATA") (pinfunction "SIM_DATA_SIM_DATA") (pintype "bidirectional"))
      (node (ref "U4") (pin "29") (pinfunction "SIM_DATA_29") (pintype "bidirectional"))
    )
    (net (code "76") (name "Net-(U4-SIM_GND)") (class "Default")
      (node (ref "U$2") (pin "SIM_GND") (pinfunction "SIM_GND_SIM_GND") (pintype "bidirectional"))
      (node (ref "U4") (pin "31") (pinfunction "SIM_GND_31") (pintype "power_in"))
    )
    (net (code "77") (name "Net-(U4-SIM_RST)") (class "Default")
      (node (ref "U$2") (pin "SIM_RST") (pinfunction "SIM_RST_SIM_RST") (pintype "bidirectional"))
      (node (ref "U4") (pin "28") (pinfunction "SIM_RST_28") (pintype "output"))
    )
    (net (code "78") (name "Net-(U4-SIM_VDD)") (class "Default")
      (node (ref "U$2") (pin "SIM_VDD") (pinfunction "SIM_VDD_SIM_VDD") (pintype "bidirectional"))
      (node (ref "U4") (pin "27") (pinfunction "SIM_VDD_27") (pintype "power_in"))
    )
    (net (code "79") (name "Net-(U4-TXD)") (class "Default")
      (node (ref "R15") (pin "1") (pinfunction "1_1") (pintype "passive"))
      (node (ref "U4") (pin "22") (pinfunction "TXD_22") (pintype "output"))
    )
    (net (code "80") (name "unconnected-(L-80-1PPS-Pad6)") (class "Default")
      (node (ref "L-80") (pin "6") (pinfunction "1PPS_6") (pintype "output"))
    )
    (net (code "81") (name "unconnected-(L-80-AADET_N-Pad8)") (class "Default")
      (node (ref "L-80") (pin "8") (pinfunction "AADET_N_8") (pintype "bidirectional"))
    )
    (net (code "82") (name "unconnected-(L-80-EX_ANT-Pad11)") (class "Default")
      (node (ref "L-80") (pin "11") (pinfunction "EX_ANT_11") (pintype "input"))
    )
    (net (code "83") (name "unconnected-(L-80-TIMER-Pad7)") (class "Default")
      (node (ref "L-80") (pin "7") (pinfunction "TIMER_7") (pintype "output"))
    )
    (net (code "84") (name "unconnected-(L-80-~{RESET}-Pad10)") (class "Default")
      (node (ref "L-80") (pin "10") (pinfunction "~{RESET}_10") (pintype "input"))
    )
    (net (code "85") (name "unconnected-(U$1-PadCD)") (class "Default")
      (node (ref "U$1") (pin "CD") (pinfunction "CD_CD") (pintype "output"))
    )
    (net (code "86") (name "unconnected-(U1-ADC6-Pad19)") (class "Default")
      (node (ref "U1") (pin "19") (pinfunction "ADC6_19") (pintype "bidirectional"))
    )
    (net (code "87") (name "unconnected-(U1-ADC7-Pad22)") (class "Default")
      (node (ref "U1") (pin "22") (pinfunction "ADC7_22") (pintype "bidirectional"))
    )
    (net (code "88") (name "unconnected-(U1-AREF-Pad20)") (class "Default")
      (node (ref "U1") (pin "20") (pinfunction "AREF_20") (pintype "bidirectional"))
    )
    (net (code "89") (name "unconnected-(U1-PB0(ICP)-Pad12)") (class "Default")
      (node (ref "U1") (pin "12") (pinfunction "PB0(ICP)_12") (pintype "bidirectional"))
    )
    (net (code "90") (name "unconnected-(U1-PB1(OC1A)-Pad13)") (class "Default")
      (node (ref "U1") (pin "13") (pinfunction "PB1(OC1A)_13") (pintype "bidirectional"))
    )
    (net (code "91") (name "unconnected-(U1-PB2(SS{slash}OC1B)-Pad14)") (class "Default")
      (node (ref "U1") (pin "14") (pinfunction "PB2(SS/OC1B)_14") (pintype "bidirectional"))
    )
    (net (code "92") (name "unconnected-(U1-PC0(ADC0)-Pad23)") (class "Default")
      (node (ref "U1") (pin "23") (pinfunction "PC0(ADC0)_23") (pintype "bidirectional"))
    )
    (net (code "93") (name "unconnected-(U1-PC1(ADC1)-Pad24)") (class "Default")
      (node (ref "U1") (pin "24") (pinfunction "PC1(ADC1)_24") (pintype "bidirectional"))
    )
    (net (code "94") (name "unconnected-(U1-PC2(ADC2)-Pad25)") (class "Default")
      (node (ref "U1") (pin "25") (pinfunction "PC2(ADC2)_25") (pintype "bidirectional"))
    )
    (net (code "95") (name "unconnected-(U1-PC3(ADC3)-Pad26)") (class "Default")
      (node (ref "U1") (pin "26") (pinfunction "PC3(ADC3)_26") (pintype "bidirectional"))
    )
    (net (code "96") (name "unconnected-(U1-PD3(INT1)-Pad1)") (class "Default")
      (node (ref "U1") (pin "1") (pinfunction "PD3(INT1)_1") (pintype "bidirectional"))
    )
    (net (code "97") (name "unconnected-(U1-PD4(XCK{slash}T0)-Pad2)") (class "Default")
      (node (ref "U1") (pin "2") (pinfunction "PD4(XCK/T0)_2") (pintype "bidirectional"))
    )
    (net (code "98") (name "unconnected-(U1-PD5(T1)-Pad9)") (class "Default")
      (node (ref "U1") (pin "9") (pinfunction "PD5(T1)_9") (pintype "bidirectional"))
    )
    (net (code "99") (name "unconnected-(U1-PD6(AIN0)-Pad10)") (class "Default")
      (node (ref "U1") (pin "10") (pinfunction "PD6(AIN0)_10") (pintype "bidirectional"))
    )
    (net (code "100") (name "unconnected-(U1-PD7(AIN1)-Pad11)") (class "Default")
      (node (ref "U1") (pin "11") (pinfunction "PD7(AIN1)_11") (pintype "bidirectional"))
    )
    (net (code "101") (name "unconnected-(U3-(A11)PC3-Pad56)") (class "Default")
      (node (ref "U3") (pin "56") (pinfunction "(A11)PC3_56") (pintype "bidirectional"))
    )
    (net (code "102") (name "unconnected-(U3-(A12)PC4-Pad57)") (class "Default")
      (node (ref "U3") (pin "57") (pinfunction "(A12)PC4_57") (pintype "bidirectional"))
    )
    (net (code "103") (name "unconnected-(U3-(A13)PC5-Pad58)") (class "Default")
      (node (ref "U3") (pin "58") (pinfunction "(A13)PC5_58") (pintype "bidirectional"))
    )
    (net (code "104") (name "unconnected-(U3-(A14)PC6-Pad59)") (class "Default")
      (node (ref "U3") (pin "59") (pinfunction "(A14)PC6_59") (pintype "bidirectional"))
    )
    (net (code "105") (name "unconnected-(U3-(A15)PC7-Pad60)") (class "Default")
      (node (ref "U3") (pin "60") (pinfunction "(A15)PC7_60") (pintype "bidirectional"))
    )
    (net (code "106") (name "unconnected-(U3-(AD0)PA0-Pad78)") (class "Default")
      (node (ref "U3") (pin "78") (pinfunction "(AD0)PA0_78") (pintype "bidirectional"))
    )
    (net (code "107") (name "unconnected-(U3-(AD1)PA1-Pad77)") (class "Default")
      (node (ref "U3") (pin "77") (pinfunction "(AD1)PA1_77") (pintype "bidirectional"))
    )
    (net (code "108") (name "unconnected-(U3-(AD2)PA2-Pad76)") (class "Default")
      (node (ref "U3") (pin "76") (pinfunction "(AD2)PA2_76") (pintype "bidirectional"))
    )
    (net (code "109") (name "unconnected-(U3-(AD3)PA3-Pad75)") (class "Default")
      (node (ref "U3") (pin "75") (pinfunction "(AD3)PA3_75") (pintype "bidirectional"))
    )
    (net (code "110") (name "unconnected-(U3-(AD4)PA4-Pad74)") (class "Default")
      (node (ref "U3") (pin "74") (pinfunction "(AD4)PA4_74") (pintype "bidirectional"))
    )
    (net (code "111") (name "unconnected-(U3-(AD5)PA5-Pad73)") (class "Default")
      (node (ref "U3") (pin "73") (pinfunction "(AD5)PA5_73") (pintype "bidirectional"))
    )
    (net (code "112") (name "unconnected-(U3-(AD6)PA6-Pad72)") (class "Default")
      (node (ref "U3") (pin "72") (pinfunction "(AD6)PA6_72") (pintype "bidirectional"))
    )
    (net (code "113") (name "unconnected-(U3-(AD7)PA7-Pad71)") (class "Default")
      (node (ref "U3") (pin "71") (pinfunction "(AD7)PA7_71") (pintype "bidirectional"))
    )
    (net (code "114") (name "unconnected-(U3-(ADC1)PF1-Pad96)") (class "Default")
      (node (ref "U3") (pin "96") (pinfunction "(ADC1)PF1_96") (pintype "bidirectional"))
    )
    (net (code "115") (name "unconnected-(U3-(ADC2)PF2-Pad95)") (class "Default")
      (node (ref "U3") (pin "95") (pinfunction "(ADC2)PF2_95") (pintype "bidirectional"))
    )
    (net (code "116") (name "unconnected-(U3-(ADC3)PF3-Pad94)") (class "Default")
      (node (ref "U3") (pin "94") (pinfunction "(ADC3)PF3_94") (pintype "bidirectional"))
    )
    (net (code "117") (name "unconnected-(U3-(ADC4{slash}TCK)PF4-Pad93)") (class "Default")
      (node (ref "U3") (pin "93") (pinfunction "(ADC4/TCK)PF4_93") (pintype "bidirectional"))
    )
    (net (code "118") (name "unconnected-(U3-(ADC5{slash}TMS)PF5-Pad92)") (class "Default")
      (node (ref "U3") (pin "92") (pinfunction "(ADC5/TMS)PF5_92") (pintype "bidirectional"))
    )
    (net (code "119") (name "unconnected-(U3-(ADC6{slash}TDO)PF6-Pad91)") (class "Default")
      (node (ref "U3") (pin "91") (pinfunction "(ADC6/TDO)PF6_91") (pintype "bidirectional"))
    )
    (net (code "120") (name "unconnected-(U3-(ADC7{slash}TDI)PF7-Pad90)") (class "Default")
      (node (ref "U3") (pin "90") (pinfunction "(ADC7/TDI)PF7_90") (pintype "bidirectional"))
    )
    (net (code "121") (name "unconnected-(U3-(ALE)PG2-Pad70)") (class "Default")
      (node (ref "U3") (pin "70") (pinfunction "(ALE)PG2_70") (pintype "bidirectional"))
    )
    (net (code "122") (name "unconnected-(U3-(CLKO{slash}ICP3{slash}INT7)PE7-Pad9)") (class "Default")
      (node (ref "U3") (pin "9") (pinfunction "(CLKO/ICP3/INT7)PE7_9") (pintype "bidirectional"))
    )
    (net (code "123") (name "unconnected-(U3-(ICP1)PD4-Pad47)") (class "Default")
      (node (ref "U3") (pin "47") (pinfunction "(ICP1)PD4_47") (pintype "bidirectional"))
    )
    (net (code "124") (name "unconnected-(U3-(OC0A{slash}OC1C{slash}PCINT7)PB7-Pad26)") (class "Default")
      (node (ref "U3") (pin "26") (pinfunction "(OC0A/OC1C/PCINT7)PB7_26") (pintype "bidirectional"))
    )
    (net (code "125") (name "unconnected-(U3-(OC0B)PG5-Pad1)") (class "Default")
      (node (ref "U3") (pin "1") (pinfunction "(OC0B)PG5_1") (pintype "bidirectional"))
    )
    (net (code "126") (name "unconnected-(U3-(OC1A{slash}PCINT5)PB5-Pad24)") (class "Default")
      (node (ref "U3") (pin "24") (pinfunction "(OC1A/PCINT5)PB5_24") (pintype "bidirectional"))
    )
    (net (code "127") (name "unconnected-(U3-(OC1B{slash}PCINT6)PB6-Pad25)") (class "Default")
      (node (ref "U3") (pin "25") (pinfunction "(OC1B/PCINT6)PB6_25") (pintype "bidirectional"))
    )
    (net (code "128") (name "unconnected-(U3-(OC2A{slash}PCINT4)PB4-Pad23)") (class "Default")
      (node (ref "U3") (pin "23") (pinfunction "(OC2A/PCINT4)PB4_23") (pintype "bidirectional"))
    )
    (net (code "129") (name "unconnected-(U3-(OC3A{slash}AIN1)PE3-Pad5)") (class "Default")
      (node (ref "U3") (pin "5") (pinfunction "(OC3A/AIN1)PE3_5") (pintype "bidirectional"))
    )
    (net (code "130") (name "unconnected-(U3-(OC3C{slash}INT5)PE5-Pad7)") (class "Default")
      (node (ref "U3") (pin "7") (pinfunction "(OC3C/INT5)PE5_7") (pintype "bidirectional"))
    )
    (net (code "131") (name "unconnected-(U3-(RD)PG1-Pad52)") (class "Default")
      (node (ref "U3") (pin "52") (pinfunction "(RD)PG1_52") (pintype "bidirectional"))
    )
    (net (code "132") (name "unconnected-(U3-(T0)PD7-Pad50)") (class "Default")
      (node (ref "U3") (pin "50") (pinfunction "(T0)PD7_50") (pintype "bidirectional"))
    )
    (net (code "133") (name "unconnected-(U3-(T1)PD6-Pad49)") (class "Default")
      (node (ref "U3") (pin "49") (pinfunction "(T1)PD6_49") (pintype "bidirectional"))
    )
    (net (code "134") (name "unconnected-(U3-(T3{slash}INT6)PE6-Pad8)") (class "Default")
      (node (ref "U3") (pin "8") (pinfunction "(T3/INT6)PE6_8") (pintype "bidirectional"))
    )
    (net (code "135") (name "unconnected-(U3-(TOSC1)PG4-Pad29)") (class "Default")
      (node (ref "U3") (pin "29") (pinfunction "(TOSC1)PG4_29") (pintype "bidirectional"))
    )
    (net (code "136") (name "unconnected-(U3-(TOSC2)PG3-Pad28)") (class "Default")
      (node (ref "U3") (pin "28") (pinfunction "(TOSC2)PG3_28") (pintype "bidirectional"))
    )
    (net (code "137") (name "unconnected-(U3-(WR)PG0-Pad51)") (class "Default")
      (node (ref "U3") (pin "51") (pinfunction "(WR)PG0_51") (pintype "bidirectional"))
    )
    (net (code "138") (name "unconnected-(U3-(XCK0{slash}AIN0)PE2-Pad4)") (class "Default")
      (node (ref "U3") (pin "4") (pinfunction "(XCK0/AIN0)PE2_4") (pintype "bidirectional"))
    )
    (net (code "139") (name "unconnected-(U3-(XCK1)PD5-Pad48)") (class "Default")
      (node (ref "U3") (pin "48") (pinfunction "(XCK1)PD5_48") (pintype "bidirectional"))
    )
    (net (code "140") (name "unconnected-(U3-AREF-Pad98)") (class "Default")
      (node (ref "U3") (pin "98") (pinfunction "AREF_98") (pintype "bidirectional"))
    )
    (net (code "141") (name "unconnected-(U3-PH2(XCK2)-Pad14)") (class "Default")
      (node (ref "U3") (pin "14") (pinfunction "PH2(XCK2)_14") (pintype "bidirectional"))
    )
    (net (code "142") (name "unconnected-(U3-PH3(OC4A)-Pad15)") (class "Default")
      (node (ref "U3") (pin "15") (pinfunction "PH3(OC4A)_15") (pintype "bidirectional"))
    )
    (net (code "143") (name "unconnected-(U3-PH4(OC4B)-Pad16)") (class "Default")
      (node (ref "U3") (pin "16") (pinfunction "PH4(OC4B)_16") (pintype "bidirectional"))
    )
    (net (code "144") (name "unconnected-(U3-PH5(OC4C)-Pad17)") (class "Default")
      (node (ref "U3") (pin "17") (pinfunction "PH5(OC4C)_17") (pintype "bidirectional"))
    )
    (net (code "145") (name "unconnected-(U3-PH6(OC2B)-Pad18)") (class "Default")
      (node (ref "U3") (pin "18") (pinfunction "PH6(OC2B)_18") (pintype "bidirectional"))
    )
    (net (code "146") (name "unconnected-(U3-PH7(T4)-Pad27)") (class "Default")
      (node (ref "U3") (pin "27") (pinfunction "PH7(T4)_27") (pintype "bidirectional"))
    )
    (net (code "147") (name "unconnected-(U3-PJ2(XCK3{slash}PCINT11)-Pad65)") (class "Default")
      (node (ref "U3") (pin "65") (pinfunction "PJ2(XCK3/PCINT11)_65") (pintype "bidirectional"))
    )
    (net (code "148") (name "unconnected-(U3-PJ3(PCINT12)-Pad66)") (class "Default")
      (node (ref "U3") (pin "66") (pinfunction "PJ3(PCINT12)_66") (pintype "bidirectional"))
    )
    (net (code "149") (name "unconnected-(U3-PJ4(PCINT13)-Pad67)") (class "Default")
      (node (ref "U3") (pin "67") (pinfunction "PJ4(PCINT13)_67") (pintype "bidirectional"))
    )
    (net (code "150") (name "unconnected-(U3-PJ5(PCINT14)-Pad68)") (class "Default")
      (node (ref "U3") (pin "68") (pinfunction "PJ5(PCINT14)_68") (pintype "bidirectional"))
    )
    (net (code "151") (name "unconnected-(U3-PJ6(PCINT15)-Pad69)") (class "Default")
      (node (ref "U3") (pin "69") (pinfunction "PJ6(PCINT15)_69") (pintype "bidirectional"))
    )
    (net (code "152") (name "unconnected-(U3-PJ7-Pad79)") (class "Default")
      (node (ref "U3") (pin "79") (pinfunction "PJ7_79") (pintype "bidirectional"))
    )
    (net (code "153") (name "unconnected-(U3-PK0(ADC8{slash}PCINT16)-Pad89)") (class "Default")
      (node (ref "U3") (pin "89") (pinfunction "PK0(ADC8/PCINT16)_89") (pintype "bidirectional"))
    )
    (net (code "154") (name "unconnected-(U3-PK1(ADC9{slash}PCINT17)-Pad88)") (class "Default")
      (node (ref "U3") (pin "88") (pinfunction "PK1(ADC9/PCINT17)_88") (pintype "bidirectional"))
    )
    (net (code "155") (name "unconnected-(U3-PK2(ADC10{slash}PCINT18)-Pad87)") (class "Default")
      (node (ref "U3") (pin "87") (pinfunction "PK2(ADC10/PCINT18)_87") (pintype "bidirectional"))
    )
    (net (code "156") (name "unconnected-(U3-PK3(ADC11{slash}PCINT19)-Pad86)") (class "Default")
      (node (ref "U3") (pin "86") (pinfunction "PK3(ADC11/PCINT19)_86") (pintype "bidirectional"))
    )
    (net (code "157") (name "unconnected-(U3-PK4(ADC12{slash}PCINT20)-Pad85)") (class "Default")
      (node (ref "U3") (pin "85") (pinfunction "PK4(ADC12/PCINT20)_85") (pintype "bidirectional"))
    )
    (net (code "158") (name "unconnected-(U3-PK5(ADC13{slash}PCINT21)-Pad84)") (class "Default")
      (node (ref "U3") (pin "84") (pinfunction "PK5(ADC13/PCINT21)_84") (pintype "bidirectional"))
    )
    (net (code "159") (name "unconnected-(U3-PK6(ADC14{slash}PCINT22)-Pad83)") (class "Default")
      (node (ref "U3") (pin "83") (pinfunction "PK6(ADC14/PCINT22)_83") (pintype "bidirectional"))
    )
    (net (code "160") (name "unconnected-(U3-PK7(ADC15{slash}PCINT23)-Pad82)") (class "Default")
      (node (ref "U3") (pin "82") (pinfunction "PK7(ADC15/PCINT23)_82") (pintype "bidirectional"))
    )
    (net (code "161") (name "unconnected-(U3-PL4(OC5B)-Pad39)") (class "Default")
      (node (ref "U3") (pin "39") (pinfunction "PL4(OC5B)_39") (pintype "bidirectional"))
    )
    (net (code "162") (name "unconnected-(U3-PL5(OC5C)-Pad40)") (class "Default")
      (node (ref "U3") (pin "40") (pinfunction "PL5(OC5C)_40") (pintype "bidirectional"))
    )
    (net (code "163") (name "unconnected-(U3-PL6-Pad41)") (class "Default")
      (node (ref "U3") (pin "41") (pinfunction "PL6_41") (pintype "bidirectional"))
    )
    (net (code "164") (name "unconnected-(U3-PL7-Pad42)") (class "Default")
      (node (ref "U3") (pin "42") (pinfunction "PL7_42") (pintype "bidirectional"))
    )
    (net (code "165") (name "unconnected-(U4-CTS-Pad23)") (class "Default")
      (node (ref "U4") (pin "23") (pinfunction "CTS_23") (pintype "output"))
    )
    (net (code "166") (name "unconnected-(U4-DBG_RXD-Pad14)") (class "Default")
      (node (ref "U4") (pin "14") (pinfunction "DBG_RXD_14") (pintype "input"))
    )
    (net (code "167") (name "unconnected-(U4-DBG_TXD-Pad15)") (class "Default")
      (node (ref "U4") (pin "15") (pinfunction "DBG_TXD_15") (pintype "output"))
    )
    (net (code "168") (name "unconnected-(U4-DCD-Pad25)") (class "Default")
      (node (ref "U4") (pin "25") (pinfunction "DCD_25") (pintype "output"))
    )
    (net (code "169") (name "unconnected-(U4-EMERG_OFF-Pad11)") (class "Default")
      (node (ref "U4") (pin "11") (pinfunction "EMERG_OFF_11") (pintype "input"))
    )
    (net (code "170") (name "unconnected-(U4-LOUDSPKN-Pad8)") (class "Default")
      (node (ref "U4") (pin "8") (pinfunction "LOUDSPKN_8") (pintype "output"))
    )
    (net (code "171") (name "unconnected-(U4-LOUDSPKP-Pad9)") (class "Default")
      (node (ref "U4") (pin "9") (pinfunction "LOUDSPKP_9") (pintype "output"))
    )
    (net (code "172") (name "unconnected-(U4-MIC1N-Pad5)") (class "Default")
      (node (ref "U4") (pin "5") (pinfunction "MIC1N_5") (pintype "input"))
    )
    (net (code "173") (name "unconnected-(U4-MIC1P-Pad4)") (class "Default")
      (node (ref "U4") (pin "4") (pinfunction "MIC1P_4") (pintype "input"))
    )
    (net (code "174") (name "unconnected-(U4-MIC2N-Pad3)") (class "Default")
      (node (ref "U4") (pin "3") (pinfunction "MIC2N_3") (pintype "input"))
    )
    (net (code "175") (name "unconnected-(U4-MIC2P-Pad2)") (class "Default")
      (node (ref "U4") (pin "2") (pinfunction "MIC2P_2") (pintype "input"))
    )
    (net (code "176") (name "unconnected-(U4-RTS-Pad24)") (class "Default")
      (node (ref "U4") (pin "24") (pinfunction "RTS_24") (pintype "input"))
    )
    (net (code "177") (name "unconnected-(U4-SPK1N-Pad6)") (class "Default")
      (node (ref "U4") (pin "6") (pinfunction "SPK1N_6") (pintype "output"))
    )
    (net (code "178") (name "unconnected-(U4-SPK1P-Pad7)") (class "Default")
      (node (ref "U4") (pin "7") (pinfunction "SPK1P_7") (pintype "output"))
    )
    (net (code "179") (name "unconnected-(U4-STATUS-Pad12)") (class "Default")
      (node (ref "U4") (pin "12") (pinfunction "STATUS_12") (pintype "output"))
    )
  )
)
